# schematic.net
KiCad netlist of a schematic drawn in EasyEDA
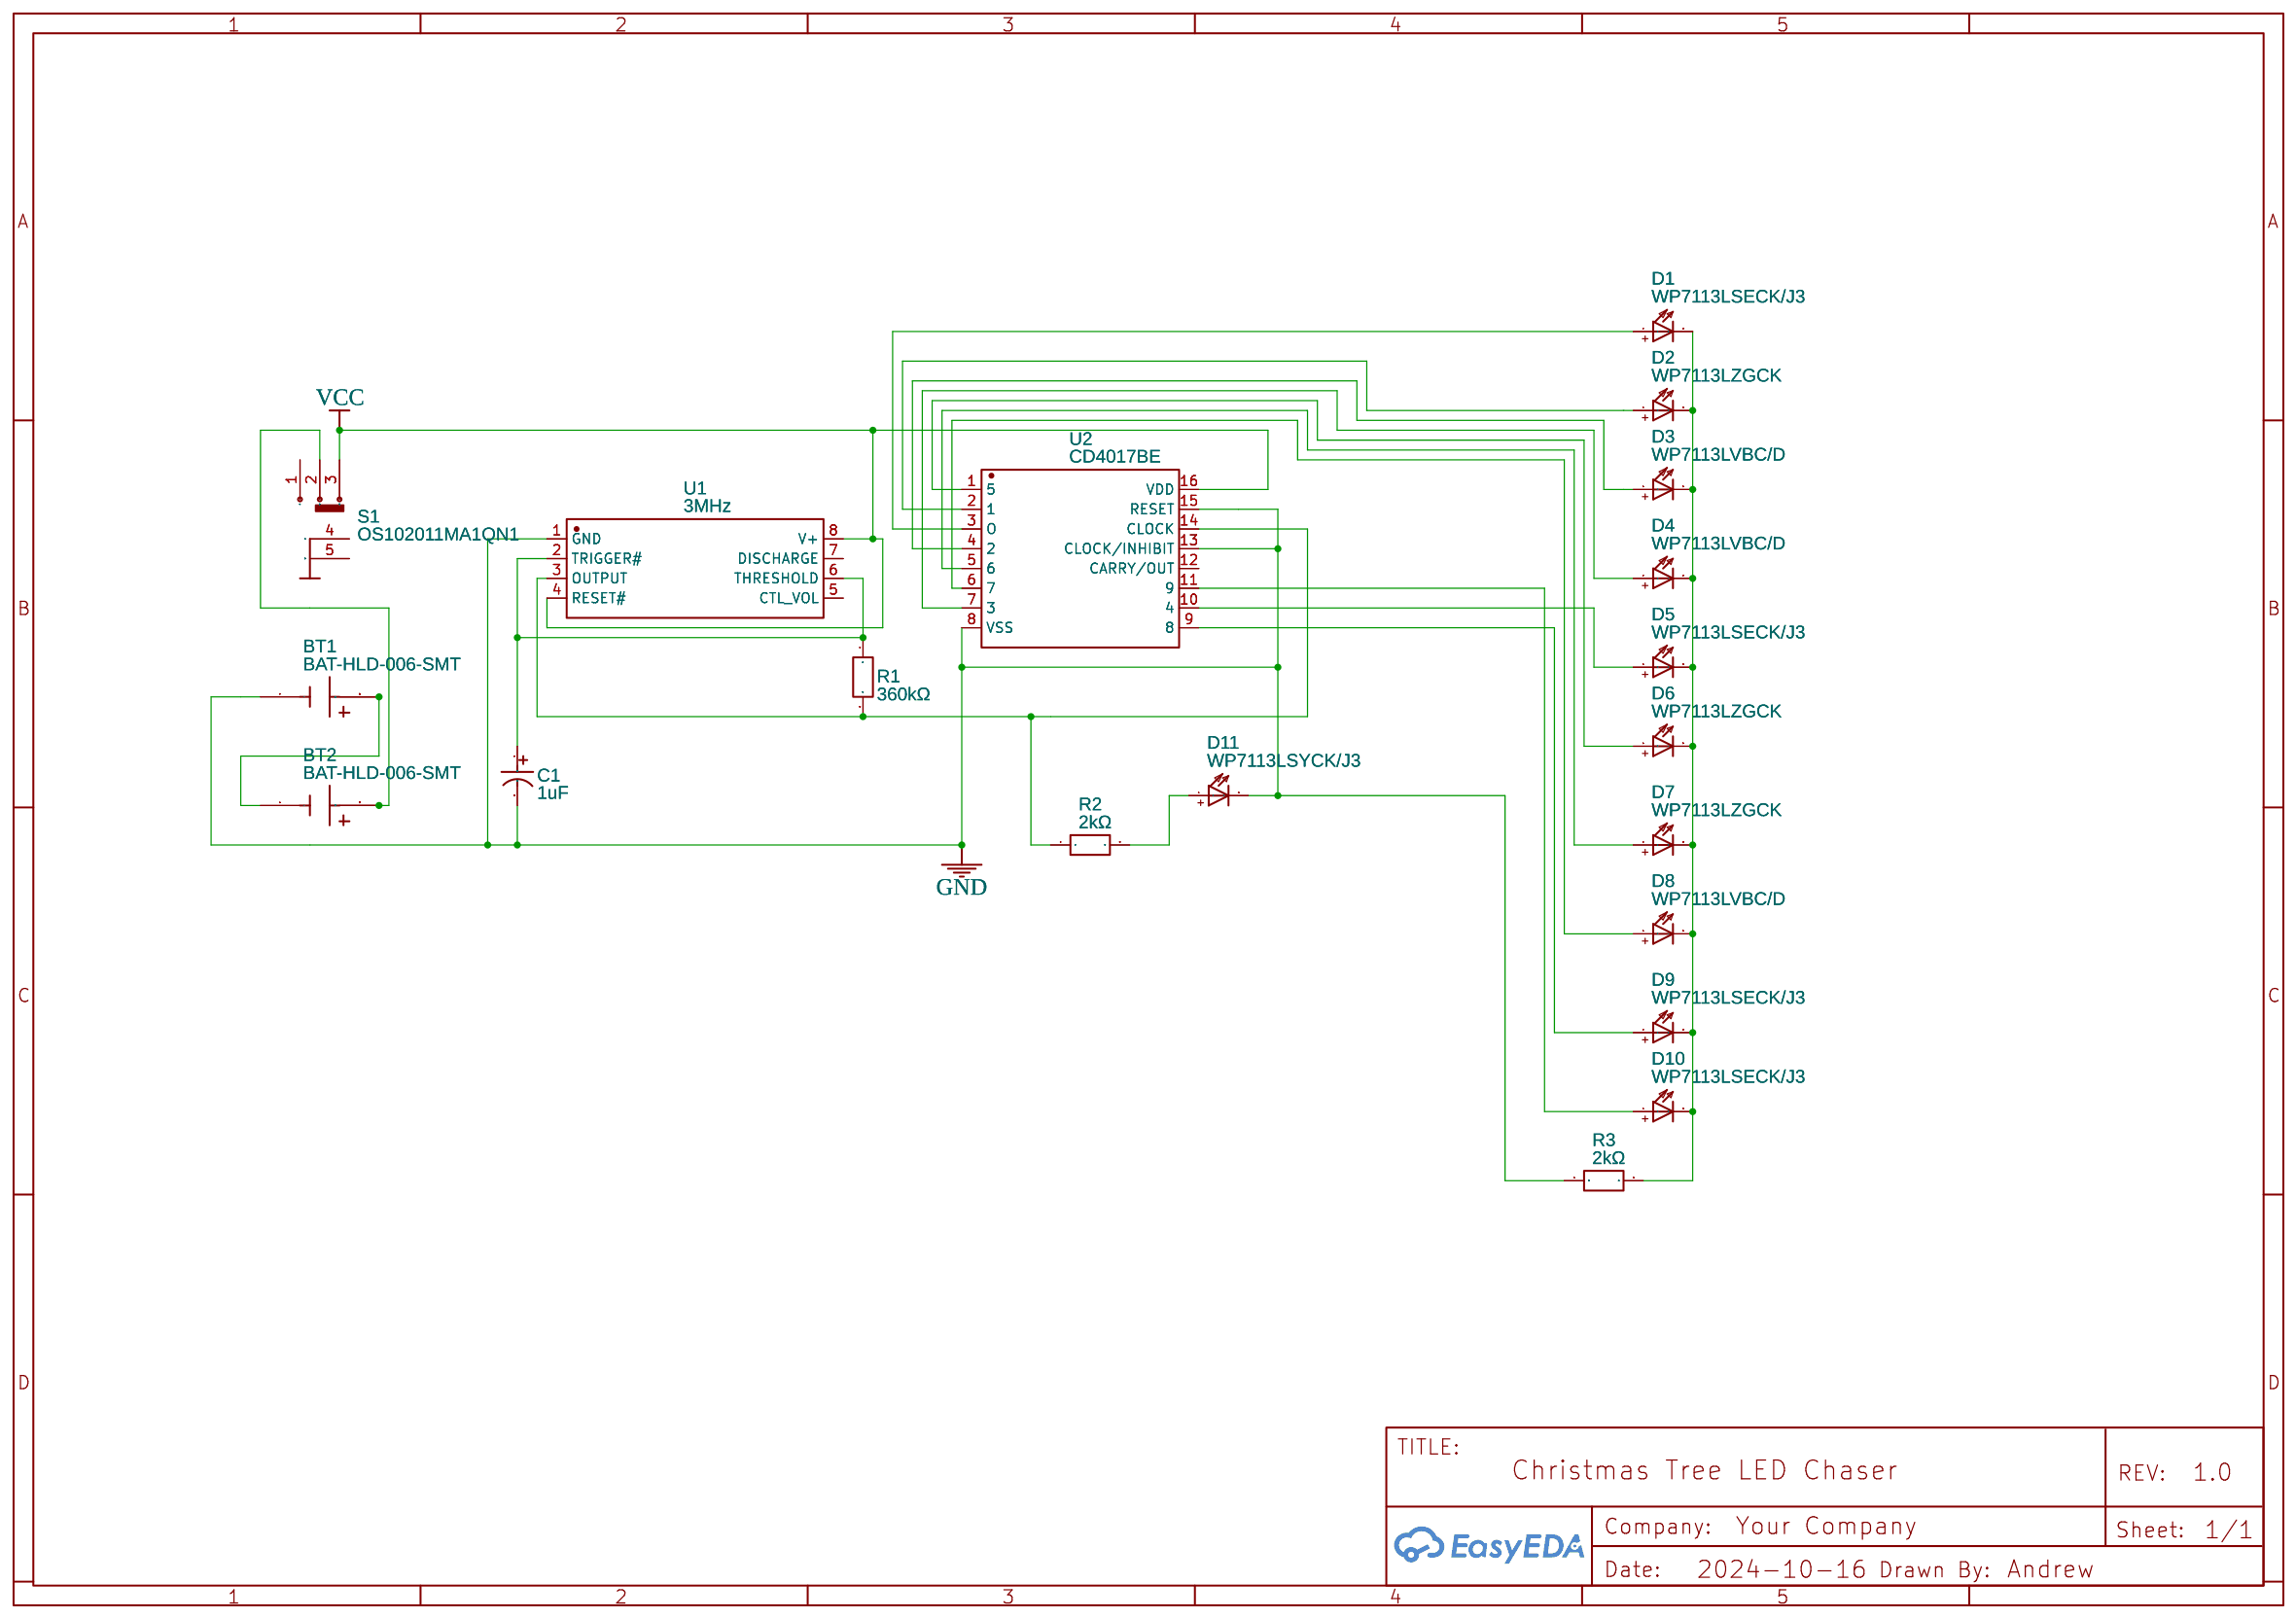
[diagram p0: schematic sheet]

(export (version "E")
  (design (tool "Eeschema 10.0.6"))
  (components
    (comp (ref "BT1") (value "BAT-HLD-006-SMT") (libsource (lib "") (part "BAT-HLD-006-SMT")))
    (comp (ref "BT2") (value "BAT-HLD-006-SMT") (libsource (lib "") (part "BAT-HLD-006-SMT")))
    (comp (ref "C1")
      (value "1uF")
      (fields (field (name "Manufacturer Part") "50YXJ1M5X11") (field (name "Manufacturer") "rubycon(红宝石)"))
      (libsource (lib "") (part "50YXJ1M5X11"))
    )
    (comp (ref "D1")
      (value "WP7113LSECK/J3")
      (fields (field (name "Manufacturer") "Kingbright"))
      (libsource (lib "") (part "WP7113LSECK/J3"))
    )
    (comp (ref "D2")
      (value "WP7113LZGCK")
      (fields (field (name "Manufacturer") "Kingbright"))
      (libsource (lib "") (part "WP7113LZGCK"))
    )
    (comp (ref "D3")
      (value "WP7113LVBC/D")
      (fields (field (name "Manufacturer") "Kingbright"))
      (libsource (lib "") (part "WP7113LVBC/D"))
    )
    (comp (ref "D4")
      (value "WP7113LVBC/D")
      (fields (field (name "Manufacturer") "Kingbright"))
      (libsource (lib "") (part "WP7113LVBC/D"))
    )
    (comp (ref "D5")
      (value "WP7113LSECK/J3")
      (fields (field (name "Manufacturer") "Kingbright"))
      (libsource (lib "") (part "WP7113LSECK/J3"))
    )
    (comp (ref "D6")
      (value "WP7113LZGCK")
      (fields (field (name "Manufacturer") "Kingbright"))
      (libsource (lib "") (part "WP7113LZGCK"))
    )
    (comp (ref "D7")
      (value "WP7113LZGCK")
      (fields (field (name "Manufacturer") "Kingbright"))
      (libsource (lib "") (part "WP7113LZGCK"))
    )
    (comp (ref "D8")
      (value "WP7113LVBC/D")
      (fields (field (name "Manufacturer") "Kingbright"))
      (libsource (lib "") (part "WP7113LVBC/D"))
    )
    (comp (ref "D9")
      (value "WP7113LSECK/J3")
      (fields (field (name "Manufacturer") "Kingbright"))
      (libsource (lib "") (part "WP7113LSECK/J3"))
    )
    (comp (ref "D10")
      (value "WP7113LSECK/J3")
      (fields (field (name "Manufacturer") "Kingbright"))
      (libsource (lib "") (part "WP7113LSECK/J3"))
    )
    (comp (ref "D11")
      (value "WP7113LSYCK/J3")
      (fields (field (name "Manufacturer") "Kingbright"))
      (libsource (lib "") (part "WP7113LSYCK/J3"))
    )
    (comp (ref "R1")
      (value "360kΩ")
      (fields
        (field (name "Manufacturer Part") "CF14JT360K")
        (field (name "Manufacturer") "SEI(Stackpole Electronics Inc.)")
      )
      (libsource (lib "") (part "CF14JT360K"))
    )
    (comp (ref "R2")
      (value "2kΩ")
      (fields
        (field (name "Manufacturer Part") "CF14JT2K00")
        (field (name "Manufacturer") "SEI(Stackpole Electronics Inc.)")
      )
      (libsource (lib "") (part "CF14JT2K00"))
    )
    (comp (ref "R3")
      (value "2kΩ")
      (fields
        (field (name "Manufacturer Part") "CF14JT2K00")
        (field (name "Manufacturer") "SEI(Stackpole Electronics Inc.)")
      )
      (libsource (lib "") (part "CF14JT2K00"))
    )
    (comp (ref "S1")
      (value "OS102011MA1QN1")
      (fields (field (name "Manufacturer") "C&K"))
      (libsource (lib "") (part "OS102011MA1QN1"))
    )
    (comp (ref "U1")
      (value "3MHz")
      (fields (field (name "Manufacturer Part") "LMC555CN/NOPB") (field (name "Manufacturer") "TI(德州仪器)"))
      (libsource (lib "") (part "LMC555CN/NOPB"))
    )
    (comp (ref "U2")
      (value "CD4017BE")
      (fields (field (name "Manufacturer") "TI(德州仪器)"))
      (libsource (lib "") (part "CD4017BE"))
    )
  )
  (nets
    (net (code "1") (name "GND") (class "Default")
      (node (ref "BT1") (pin "N") (pinfunction "-_N") (pintype "bidirectional"))
      (node (ref "C1") (pin "2") (pinfunction "2_2") (pintype "input"))
      (node (ref "D11") (pin "2") (pinfunction "-_2") (pintype "bidirectional"))
      (node (ref "R3") (pin "1") (pinfunction "1_1") (pintype "unspecified"))
      (node (ref "U1") (pin "1") (pinfunction "GND_1") (pintype "unspecified"))
      (node (ref "U2") (pin "13") (pinfunction "CLOCK/INHIBIT_13") (pintype "unspecified"))
      (node (ref "U2") (pin "15") (pinfunction "RESET_15") (pintype "unspecified"))
      (node (ref "U2") (pin "8") (pinfunction "VSS_8") (pintype "unspecified"))
    )
    (net (code "2") (name "Net-(BT2-+-PadP1)") (class "Default")
      (node (ref "BT2") (pin "P1") (pinfunction "+_P1") (pintype "bidirectional"))
      (node (ref "BT2") (pin "P2") (pinfunction "+_P2") (pintype "bidirectional"))
      (node (ref "S1") (pin "2") (pinfunction "2_2") (pintype "unspecified"))
    )
    (net (code "3") (name "Net-(BT2--)") (class "Default")
      (node (ref "BT1") (pin "P1") (pinfunction "+_P1") (pintype "bidirectional"))
      (node (ref "BT1") (pin "P2") (pinfunction "+_P2") (pintype "bidirectional"))
      (node (ref "BT2") (pin "N") (pinfunction "-_N") (pintype "bidirectional"))
    )
    (net (code "4") (name "Net-(D1-+)") (class "Default")
      (node (ref "D1") (pin "1") (pinfunction "+_1") (pintype "bidirectional"))
      (node (ref "U2") (pin "3") (pinfunction "O_3") (pintype "unspecified"))
    )
    (net (code "5") (name "Net-(D1--)") (class "Default")
      (node (ref "D1") (pin "2") (pinfunction "-_2") (pintype "bidirectional"))
      (node (ref "D10") (pin "2") (pinfunction "-_2") (pintype "bidirectional"))
      (node (ref "D2") (pin "2") (pinfunction "-_2") (pintype "bidirectional"))
      (node (ref "D3") (pin "2") (pinfunction "-_2") (pintype "bidirectional"))
      (node (ref "D4") (pin "2") (pinfunction "-_2") (pintype "bidirectional"))
      (node (ref "D5") (pin "2") (pinfunction "-_2") (pintype "bidirectional"))
      (node (ref "D6") (pin "2") (pinfunction "-_2") (pintype "bidirectional"))
      (node (ref "D7") (pin "2") (pinfunction "-_2") (pintype "bidirectional"))
      (node (ref "D8") (pin "2") (pinfunction "-_2") (pintype "bidirectional"))
      (node (ref "D9") (pin "2") (pinfunction "-_2") (pintype "bidirectional"))
      (node (ref "R3") (pin "2") (pinfunction "2_2") (pintype "unspecified"))
    )
    (net (code "6") (name "Net-(D2-+)") (class "Default")
      (node (ref "D2") (pin "1") (pinfunction "+_1") (pintype "bidirectional"))
      (node (ref "U2") (pin "2") (pinfunction "1_2") (pintype "unspecified"))
    )
    (net (code "7") (name "Net-(D3-+)") (class "Default")
      (node (ref "D3") (pin "1") (pinfunction "+_1") (pintype "bidirectional"))
      (node (ref "U2") (pin "4") (pinfunction "2_4") (pintype "unspecified"))
    )
    (net (code "8") (name "Net-(D4-+)") (class "Default")
      (node (ref "D4") (pin "1") (pinfunction "+_1") (pintype "bidirectional"))
      (node (ref "U2") (pin "7") (pinfunction "3_7") (pintype "unspecified"))
    )
    (net (code "9") (name "Net-(D5-+)") (class "Default")
      (node (ref "D5") (pin "1") (pinfunction "+_1") (pintype "bidirectional"))
      (node (ref "U2") (pin "10") (pinfunction "4_10") (pintype "unspecified"))
    )
    (net (code "10") (name "Net-(D6-+)") (class "Default")
      (node (ref "D6") (pin "1") (pinfunction "+_1") (pintype "bidirectional"))
      (node (ref "U2") (pin "1") (pinfunction "5_1") (pintype "unspecified"))
    )
    (net (code "11") (name "Net-(D7-+)") (class "Default")
      (node (ref "D7") (pin "1") (pinfunction "+_1") (pintype "bidirectional"))
      (node (ref "U2") (pin "5") (pinfunction "6_5") (pintype "unspecified"))
    )
    (net (code "12") (name "Net-(D8-+)") (class "Default")
      (node (ref "D8") (pin "1") (pinfunction "+_1") (pintype "bidirectional"))
      (node (ref "U2") (pin "6") (pinfunction "7_6") (pintype "unspecified"))
    )
    (net (code "13") (name "Net-(D9-+)") (class "Default")
      (node (ref "D9") (pin "1") (pinfunction "+_1") (pintype "bidirectional"))
      (node (ref "U2") (pin "9") (pinfunction "8_9") (pintype "unspecified"))
    )
    (net (code "14") (name "Net-(D10-+)") (class "Default")
      (node (ref "D10") (pin "1") (pinfunction "+_1") (pintype "bidirectional"))
      (node (ref "U2") (pin "11") (pinfunction "9_11") (pintype "unspecified"))
    )
    (net (code "15") (name "Net-(D11-+)") (class "Default")
      (node (ref "D11") (pin "1") (pinfunction "+_1") (pintype "bidirectional"))
      (node (ref "R2") (pin "2") (pinfunction "2_2") (pintype "unspecified"))
    )
    (net (code "16") (name "Net-(U1-OUTPUT)") (class "Default")
      (node (ref "R1") (pin "2") (pinfunction "2_2") (pintype "unspecified"))
      (node (ref "R2") (pin "1") (pinfunction "1_1") (pintype "unspecified"))
      (node (ref "U1") (pin "3") (pinfunction "OUTPUT_3") (pintype "unspecified"))
      (node (ref "U2") (pin "14") (pinfunction "CLOCK_14") (pintype "unspecified"))
    )
    (net (code "17") (name "Net-(U1-THRESHOLD)") (class "Default")
      (node (ref "C1") (pin "1") (pinfunction "1_1") (pintype "input"))
      (node (ref "R1") (pin "1") (pinfunction "1_1") (pintype "unspecified"))
      (node (ref "U1") (pin "2") (pinfunction "TRIGGER#_2") (pintype "unspecified"))
      (node (ref "U1") (pin "6") (pinfunction "THRESHOLD_6") (pintype "unspecified"))
    )
    (net (code "18") (name "VCC") (class "Default")
      (node (ref "S1") (pin "3") (pinfunction "3_3") (pintype "unspecified"))
      (node (ref "U1") (pin "4") (pinfunction "RESET#_4") (pintype "unspecified"))
      (node (ref "U1") (pin "8") (pinfunction "V+_8") (pintype "unspecified"))
      (node (ref "U2") (pin "16") (pinfunction "VDD_16") (pintype "unspecified"))
    )
    (net (code "19") (name "unconnected-(S1-Pad1)") (class "Default")
      (node (ref "S1") (pin "1") (pinfunction "1_1") (pintype "unspecified"))
    )
    (net (code "20") (name "unconnected-(S1-Pad4)") (class "Default")
      (node (ref "S1") (pin "4") (pinfunction "4_4") (pintype "unspecified"))
    )
    (net (code "21") (name "unconnected-(S1-Pad5)") (class "Default")
      (node (ref "S1") (pin "5") (pinfunction "5_5") (pintype "unspecified"))
    )
    (net (code "22") (name "unconnected-(U1-CTL_VOL-Pad5)") (class "Default")
      (node (ref "U1") (pin "5") (pinfunction "CTL_VOL_5") (pintype "unspecified"))
    )
    (net (code "23") (name "unconnected-(U1-DISCHARGE-Pad7)") (class "Default")
      (node (ref "U1") (pin "7") (pinfunction "DISCHARGE_7") (pintype "unspecified"))
    )
    (net (code "24") (name "unconnected-(U2-CARRY{slash}OUT-Pad12)") (class "Default")
      (node (ref "U2") (pin "12") (pinfunction "CARRY/OUT_12") (pintype "unspecified"))
    )
  )
)
